# STeaMi-FP15-Memoire_flash.net
KiCad netlist of a schematic drawn in Altium Designer
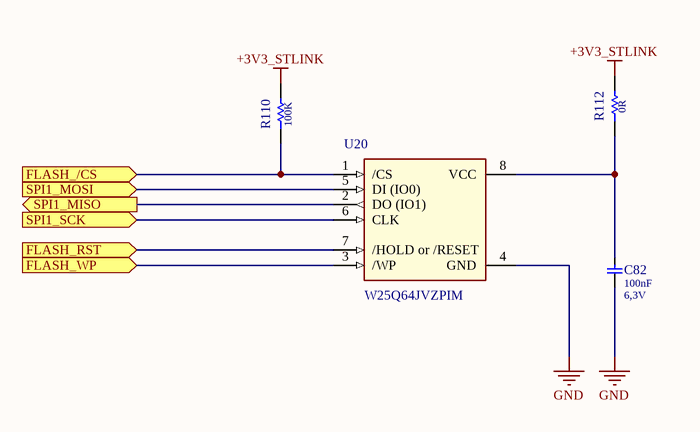
[diagram p0: STeaMi-FP15-Memoire_flash.SchDoc]

(export (version "E")
  (design (tool "Eeschema 10.0.6"))
  (components
    (comp (ref "C82")
      (value "~")
      (footprint "0402-CAP")
      (description "CAP CER 100nF 6,3V X5R 0402")
      (fields
        (field (name "MANUFACTURER") "Kyocera AVX")
        (field (name "MANUFACTURER PART NUMBER") "0402YD104KAT2A")
        (field (name "CAPACITANCE") "100nF")
        (field (name "VOLTAGE") "6,3V")
        (field (name "CREATED BY") "EAG")
        (field (name "CHECKED BY") "*")
      )
      (libsource (lib "ComponentDB") (part "CAP_SYMBOL"))
    )
    (comp (ref "R110")
      (value "~")
      (footprint "RESC1005X40N_0402")
      (description "RES CMS 100K5%-0,0625W-0402 ±100ppm/°C")
      (fields
        (field (name "MANUFACTURER") "Yageo")
        (field (name "MANUFACTURER PART NUMBER") "RC0402JR-07100KL")
        (field (name "RESISTANCE") "100K")
        (field (name "CREATED BY") "EAG")
      )
      (libsource (lib "ComponentDB") (part "RES_SYMBOL"))
    )
    (comp (ref "R112")
      (value "~")
      (footprint "RESC1005X40N_0402")
      (description "RES CMS 0R5%-0,0625W-0402")
      (fields
        (field (name "MANUFACTURER") "Yageo")
        (field (name "MANUFACTURER PART NUMBER") "RC0402JR-100RL")
        (field (name "RESISTANCE") "0R")
        (field (name "CREATED BY") "EAG")
      )
      (libsource (lib "ComponentDB") (part "RES_SYMBOL"))
    )
    (comp (ref "U20")
      (value "~")
      (footprint "SON127P600X500X80-9N")
      (description "FLASH - NOR Mémoire IC 64Mb (8M x 8) SPI - I/O quadruple, QPI, DTR 133MHz 6ns 8-WSON (6x5)")
      (fields
        (field (name "MANUFACTURER") "Winbond")
        (field (name "MANUFACTURER PART NUMBER") "W25Q64JVZPIM")
        (field (name "PART NUMBER") "W25Q64JVZPIM")
        (field (name "CREATED BY") "EAG")
        (field (name "CHECKED BY") "*")
      )
      (libsource (lib "ComponentDB") (part "W25Q64JVZPIM"))
    )
  )
  (nets
    (net (code "1") (name "+3V3_STLINK") (class "Default")
      (node (ref "R110") (pin "2") (pinfunction "2_2") (pintype "passive"))
      (node (ref "R112") (pin "2") (pinfunction "2_2") (pintype "passive"))
    )
    (net (code "2") (name "/FLASH_RST") (class "Default")
      (node (ref "U20") (pin "7") (pinfunction "/HOLD_or_/RESET_7") (pintype "input"))
    )
    (net (code "3") (name "/FLASH_WP") (class "Default")
      (node (ref "U20") (pin "3") (pinfunction "/WP_3") (pintype "input"))
    )
    (net (code "4") (name "/FLASH_{slash}CS") (class "Default")
      (node (ref "R110") (pin "1") (pinfunction "1_1") (pintype "passive"))
      (node (ref "U20") (pin "1") (pinfunction "/CS_1") (pintype "input"))
    )
    (net (code "5") (name "/SPI1_MISO") (class "Default")
      (node (ref "U20") (pin "2") (pinfunction "DO_(IO1)_2") (pintype "output"))
    )
    (net (code "6") (name "/SPI1_MOSI") (class "Default")
      (node (ref "U20") (pin "5") (pinfunction "DI_(IO0)_5") (pintype "input"))
    )
    (net (code "7") (name "/SPI1_SCK") (class "Default")
      (node (ref "U20") (pin "6") (pinfunction "CLK_6") (pintype "input"))
    )
    (net (code "8") (name "GND") (class "Default")
      (node (ref "C82") (pin "1") (pinfunction "1_1") (pintype "passive"))
      (node (ref "U20") (pin "4") (pinfunction "GND_4") (pintype "power_in"))
    )
    (net (code "9") (name "Net-(U20-VCC)") (class "Default")
      (node (ref "C82") (pin "2") (pinfunction "2_2") (pintype "passive"))
      (node (ref "R112") (pin "1") (pinfunction "1_1") (pintype "passive"))
      (node (ref "U20") (pin "8") (pinfunction "VCC_8") (pintype "power_in"))
    )
  )
)
